# LTX-Rapidfire.net
KiCad netlist of a schematic drawn in EAGLE
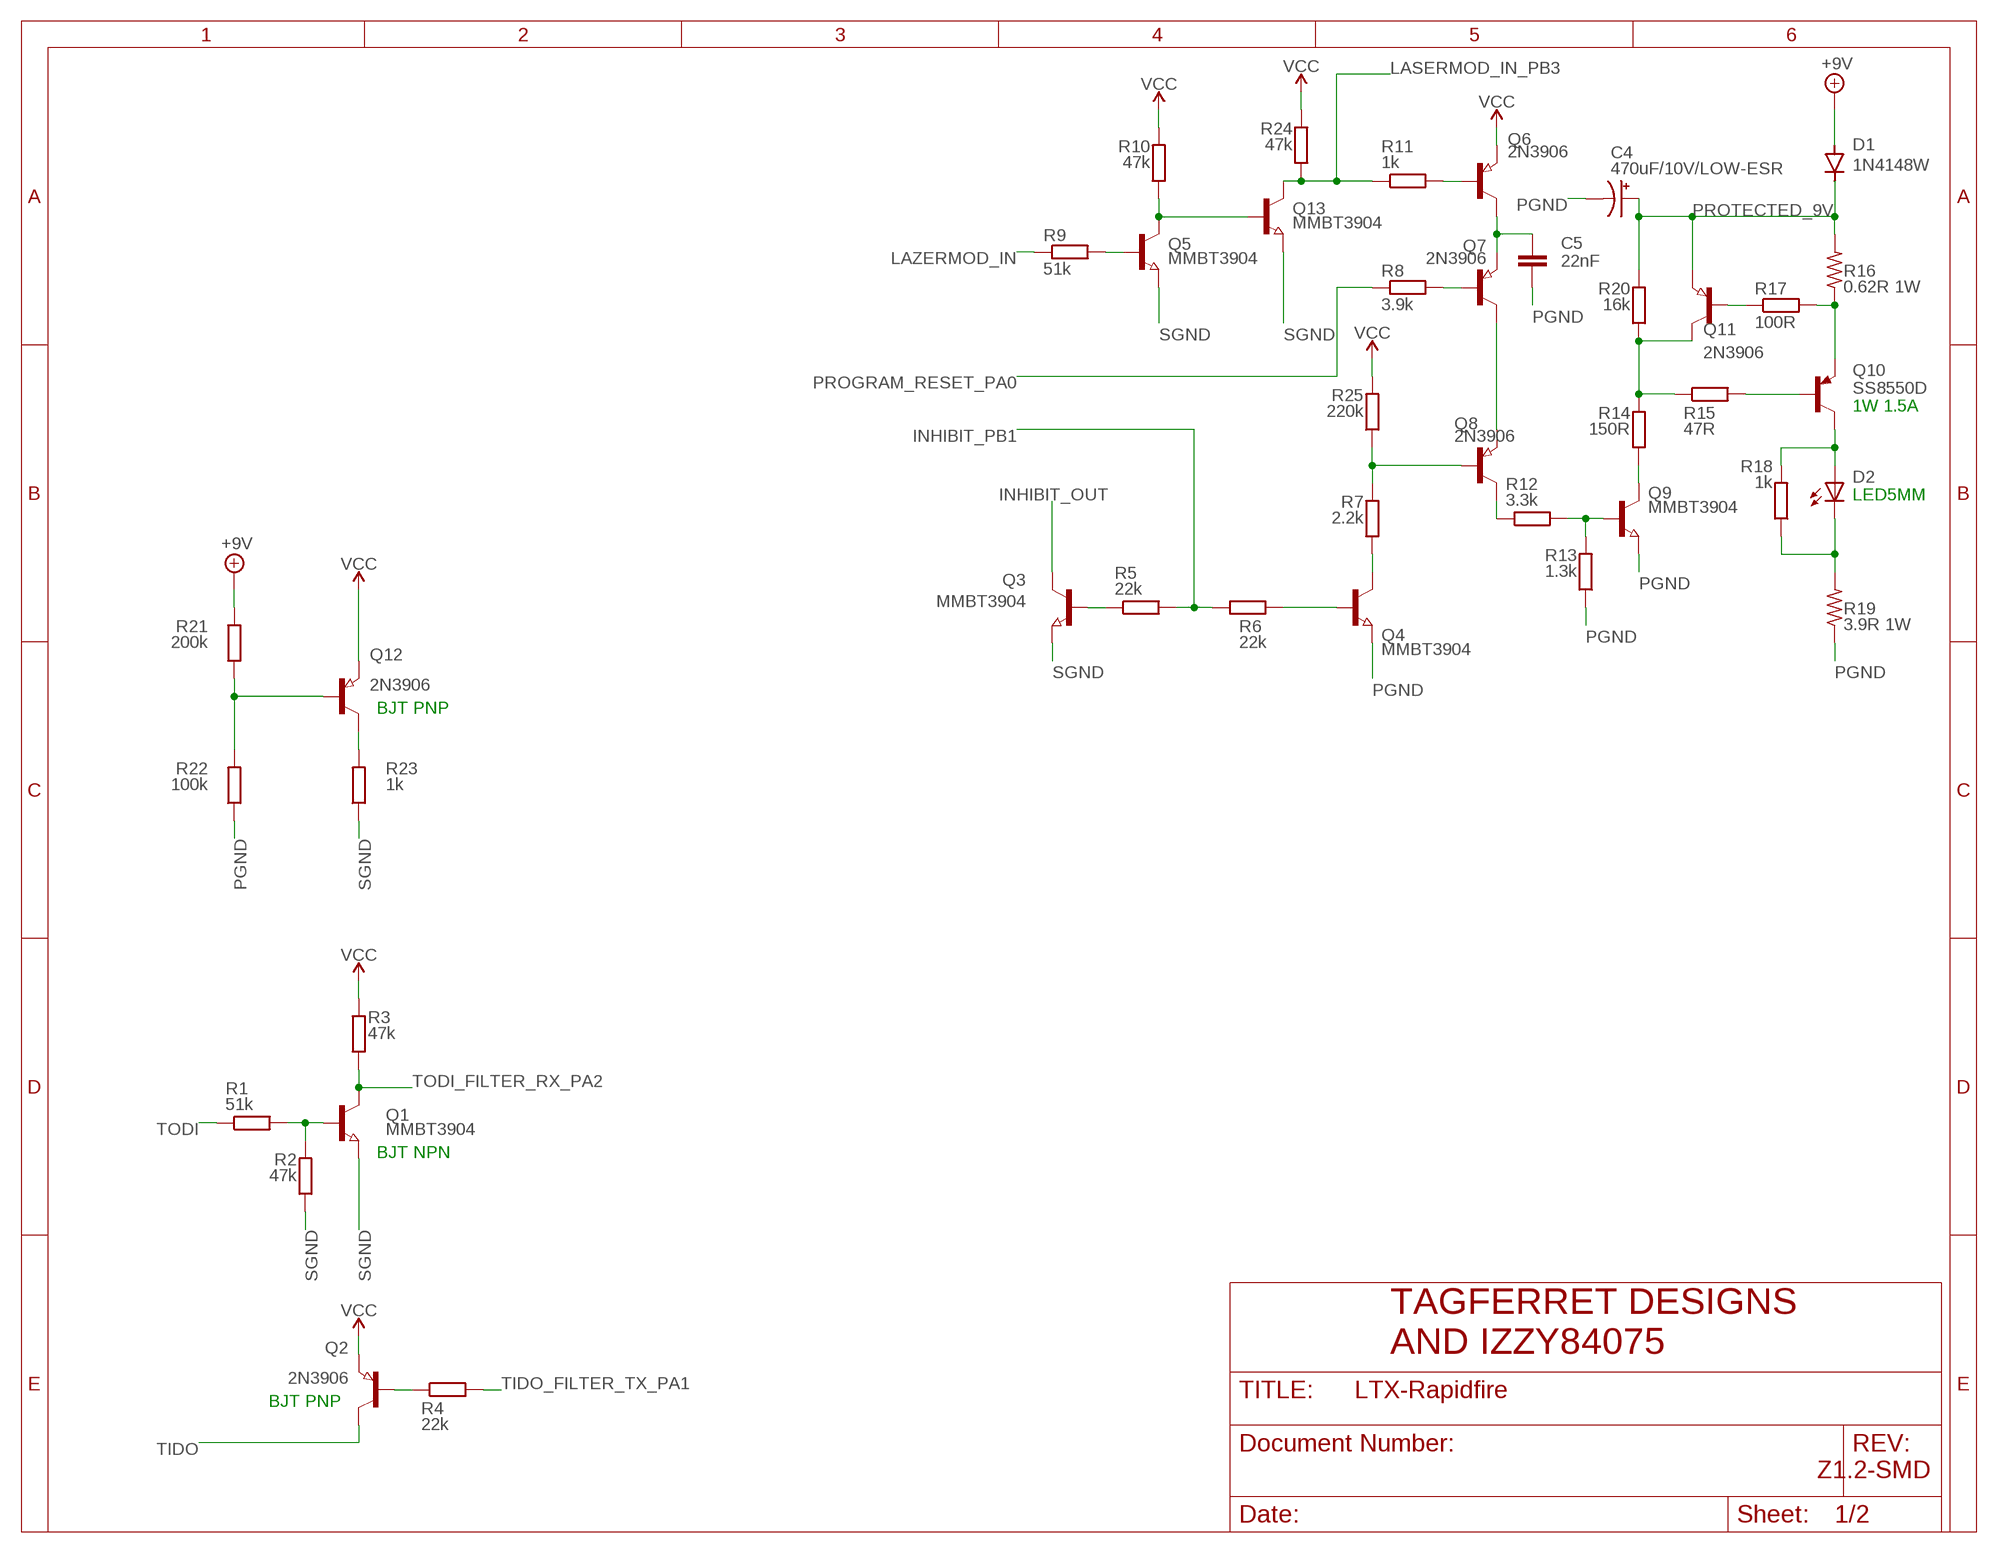
[diagram p0: schematic, sheet 1]
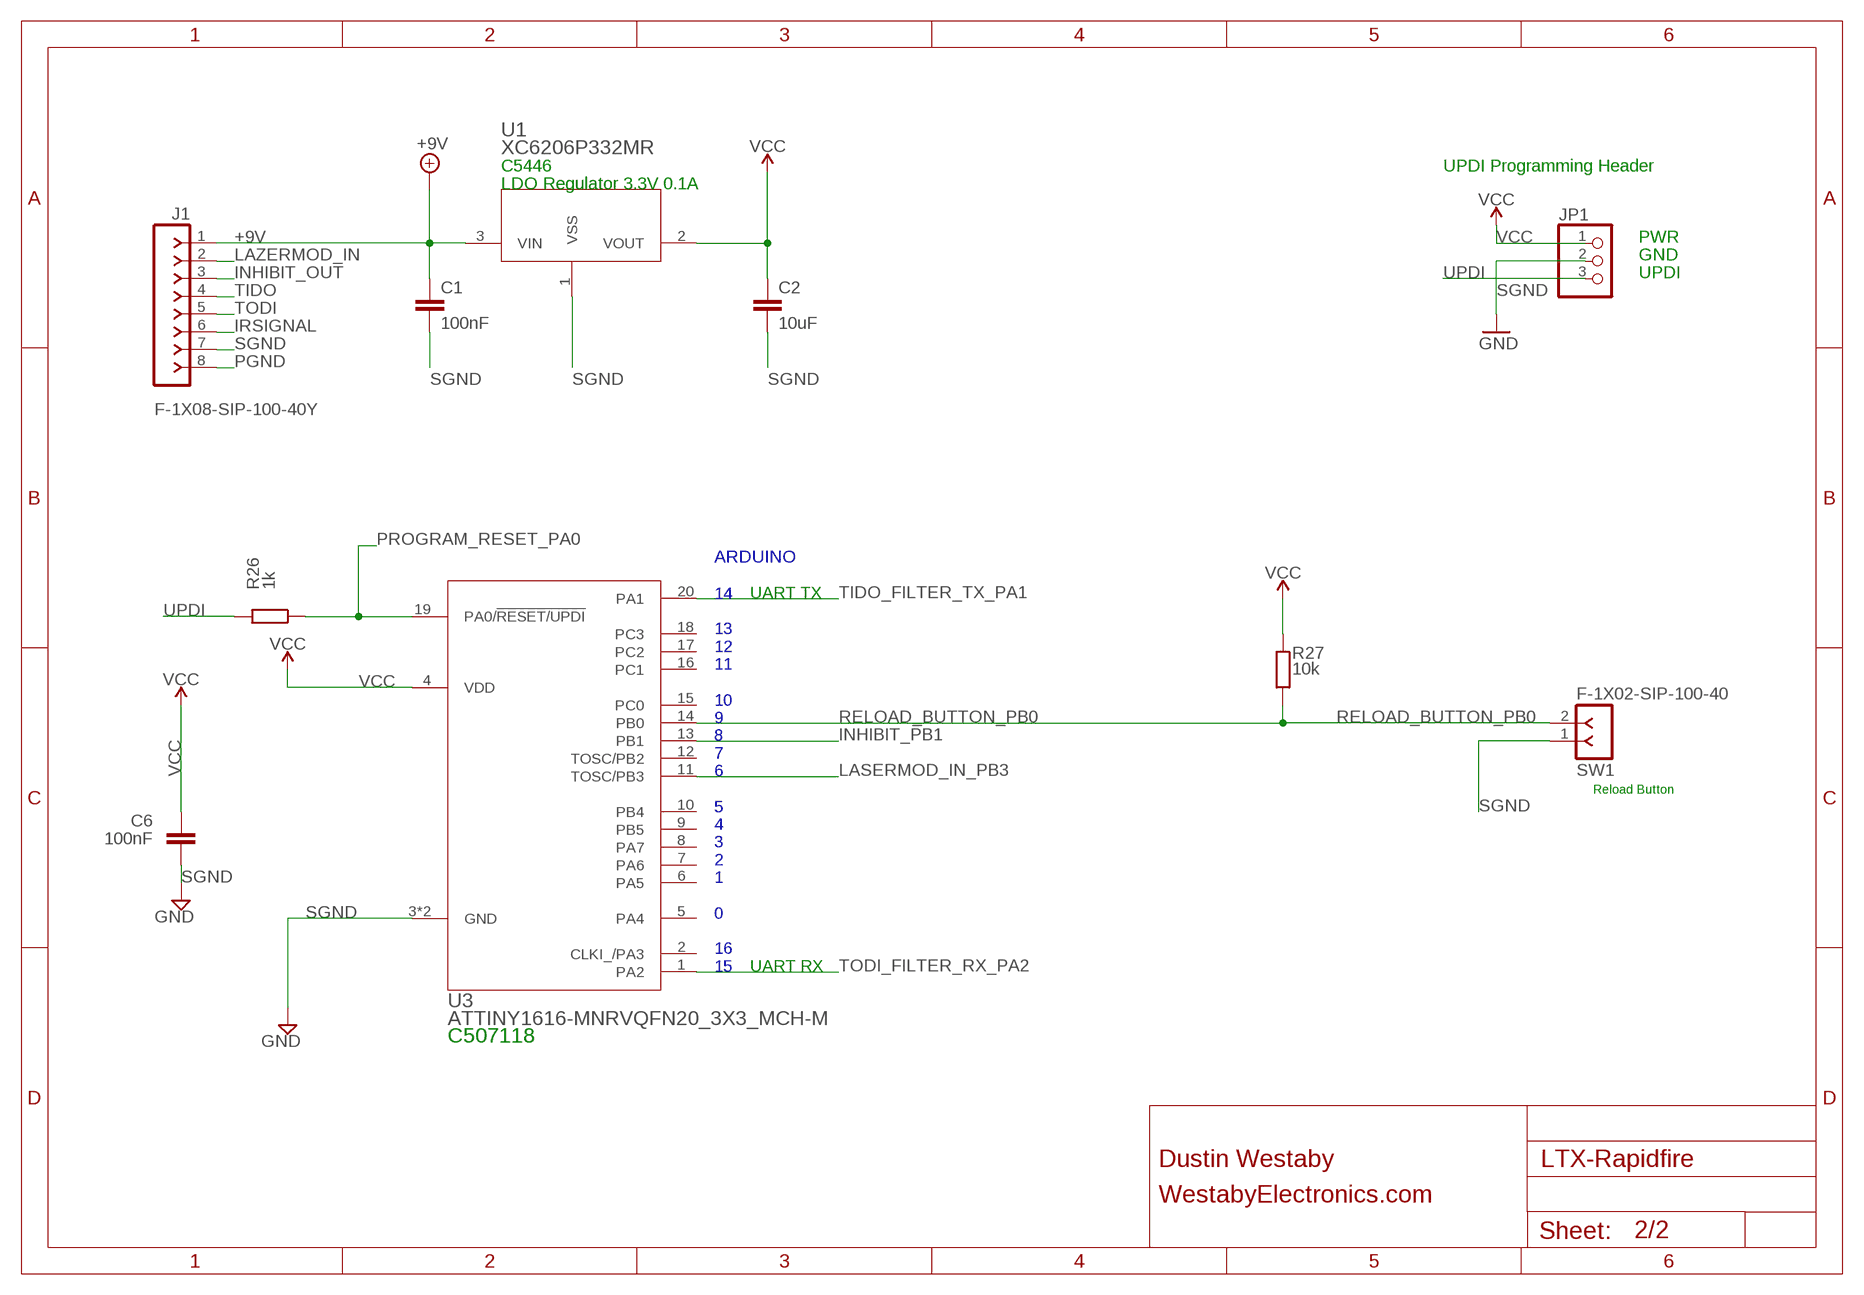
[diagram p1: schematic, sheet 2]

(export (version "E")
  (design (tool "Eeschema 10.0.6"))
  (components
    (comp (ref "C1")
      (value "100nF")
      (footprint "eagle-import:C0603")
      (fields (field (name "LCSC_PART") "C14663"))
      (libsource (lib "eagle-import") (part "C__0603100NF/50V"))
    )
    (comp (ref "C2")
      (value "10uF")
      (footprint "eagle-import:C0603")
      (fields (field (name "LCSC_PART") "C96446"))
      (libsource (lib "eagle-import") (part "C__060310UF/25V"))
    )
    (comp (ref "C6")
      (value "100nF")
      (footprint "eagle-import:C0603")
      (fields (field (name "LCSC_PART") "C14663"))
      (libsource (lib "eagle-import") (part "C__0603100NF/50V"))
    )
    (comp (ref "J1")
      (value "F-1X08-SIP-100-40Y")
      (footprint "eagle-import:SIP-100-08-40Y")
      (libsource (lib "eagle-import") (part "F-1X08-SIP-100-40Y"))
    )
    (comp (ref "JP1")
      (value "PINHD-1X3")
      (footprint "eagle-import:1X03")
      (libsource (lib "eagle-import") (part "PINHD-1X3"))
    )
    (comp (ref "R26")
      (value "1k")
      (footprint "eagle-import:R0603")
      (fields (field (name "LCSC_PART") "C21190"))
      (libsource (lib "eagle-import") (part "R__06031K"))
    )
    (comp (ref "R27")
      (value "10k")
      (footprint "eagle-import:R0603")
      (fields (field (name "LCSC_PART") "C25804"))
      (libsource (lib "eagle-import") (part "R__060310K"))
    )
    (comp (ref "SW1")
      (value "F-1X02-SIP-100-40")
      (footprint "eagle-import:SIP-100-02-40")
      (libsource (lib "eagle-import") (part "F-1X02-SIP-100-40"))
    )
    (comp (ref "U1")
      (value "XC6206P332MR")
      (footprint "eagle-import:SOT-23_TOR")
      (fields
        (field (name "LCSC_PART") "C5446")
        (field (name "COPYRIGHT") "Copyright (C) 2022 Ultra Librarian. All rights reserved.")
      )
      (libsource (lib "eagle-import") (part "XC6206P332MR"))
    )
    (comp (ref "U3")
      (value "ATTINY1616-MNRVQFN20_3X3_MCH-M")
      (footprint "eagle-import:VQFN20_3X3_MCH-M")
      (fields
        (field (name "MANUFACTURER_PART_NUMBER") "ATTINY1616-MNR")
        (field (name "COPYRIGHT") "Copyright (C) 2022 Ultra Librarian. All rights reserved.")
      )
      (libsource (lib "eagle-import") (part "ATTINY1616-MNRVQFN20_3X3_MCH-M"))
    )
    (comp (ref "C4")
      (value "470uF/10V/LOW-ESR")
      (footprint "eagle-import:E3,5-8")
      (fields (field (name "LCSC_PART") "C43332"))
      (libsource (lib "eagle-import") (part "CPOL-USE3.5-8"))
    )
    (comp (ref "C5")
      (value "22nF")
      (footprint "eagle-import:C0603")
      (fields (field (name "LCSC_PART") "C21122"))
      (libsource (lib "eagle-import") (part "C__060322NF/50V"))
    )
    (comp (ref "D1")
      (value "1N4148W")
      (footprint "eagle-import:SOD123")
      (fields (field (name "LCSC_PART") "C81598"))
      (libsource (lib "eagle-import") (part "D__SOD1231N4148W_ST"))
    )
    (comp (ref "D2")
      (value "LED5MM")
      (footprint "eagle-import:LED5MM")
      (libsource (lib "eagle-import") (part "LED5MM"))
    )
    (comp (ref "Q1")
      (value "MMBT3904")
      (footprint "eagle-import:SOT23")
      (fields (field (name "LCSC_PART") "C20526"))
      (libsource (lib "eagle-import") (part "T_NPN__SOT23-BECMMBT3904_CHANGJ"))
    )
    (comp (ref "Q2")
      (value "2N3906")
      (footprint "eagle-import:SOT23")
      (fields
        (field (name "LCSC_PART") "C8326")
        (field (name "LCSC_DATASHEET") "https://datasheet.lcsc.com/lcsc/1810111520_KEC-Semicon-2N3906S-RTK-P_C147294.pdf")
        (field (name "LCSC_PART_1") "C147294")
        (field (name "PROPERTIES") "40V 350mW 200mA 100@10mA,1V 250MHz 400mV@50mA,5mA PNP")
      )
      (libsource (lib "eagle-import") (part "T_PNP__SOT23-BECMMBT5401_CHANGJ"))
    )
    (comp (ref "Q3")
      (value "MMBT3904")
      (footprint "eagle-import:SOT23")
      (fields (field (name "LCSC_PART") "C20526"))
      (libsource (lib "eagle-import") (part "T_NPN__SOT23-BECMMBT3904_CHANGJ"))
    )
    (comp (ref "Q4")
      (value "MMBT3904")
      (footprint "eagle-import:SOT23")
      (fields (field (name "LCSC_PART") "C20526"))
      (libsource (lib "eagle-import") (part "T_NPN__SOT23-BECMMBT3904_CHANGJ"))
    )
    (comp (ref "Q5")
      (value "MMBT3904")
      (footprint "eagle-import:SOT23")
      (fields (field (name "LCSC_PART") "C20526"))
      (libsource (lib "eagle-import") (part "T_NPN__SOT23-BECMMBT3904_CHANGJ"))
    )
    (comp (ref "Q6")
      (value "2N3906")
      (footprint "eagle-import:SOT23")
      (fields
        (field (name "LCSC_PART") "C8326")
        (field (name "LCSC_DATASHEET") "https://datasheet.lcsc.com/lcsc/1810111520_KEC-Semicon-2N3906S-RTK-P_C147294.pdf")
        (field (name "LCSC_PART_1") "C147294")
        (field (name "PROPERTIES") "40V 350mW 200mA 100@10mA,1V 250MHz 400mV@50mA,5mA PNP")
      )
      (libsource (lib "eagle-import") (part "T_PNP__SOT23-BECMMBT5401_CHANGJ"))
    )
    (comp (ref "Q7")
      (value "2N3906")
      (footprint "eagle-import:SOT23")
      (fields
        (field (name "LCSC_PART") "C8326")
        (field (name "LCSC_DATASHEET") "https://datasheet.lcsc.com/lcsc/1810111520_KEC-Semicon-2N3906S-RTK-P_C147294.pdf")
        (field (name "LCSC_PART_1") "C147294")
        (field (name "PROPERTIES") "40V 350mW 200mA 100@10mA,1V 250MHz 400mV@50mA,5mA PNP")
      )
      (libsource (lib "eagle-import") (part "T_PNP__SOT23-BECMMBT5401_CHANGJ"))
    )
    (comp (ref "Q8")
      (value "2N3906")
      (footprint "eagle-import:SOT23")
      (fields
        (field (name "LCSC_PART") "C8326")
        (field (name "LCSC_DATASHEET") "https://datasheet.lcsc.com/lcsc/1810111520_KEC-Semicon-2N3906S-RTK-P_C147294.pdf")
        (field (name "LCSC_PART_1") "C147294")
        (field (name "PROPERTIES") "40V 350mW 200mA 100@10mA,1V 250MHz 400mV@50mA,5mA PNP")
      )
      (libsource (lib "eagle-import") (part "T_PNP__SOT23-BECMMBT5401_CHANGJ"))
    )
    (comp (ref "Q9")
      (value "MMBT3904")
      (footprint "eagle-import:SOT23")
      (fields (field (name "LCSC_PART") "C20526"))
      (libsource (lib "eagle-import") (part "T_NPN__SOT23-BECMMBT3904_CHANGJ"))
    )
    (comp (ref "Q10")
      (value "SS8550D")
      (footprint "eagle-import:TO92")
      (fields (field (name "LCSC_PART") "C118551"))
      (libsource (lib "eagle-import") (part "2N3906"))
    )
    (comp (ref "Q11")
      (value "2N3906")
      (footprint "eagle-import:SOT23")
      (fields
        (field (name "LCSC_PART") "C8326")
        (field (name "LCSC_DATASHEET") "https://datasheet.lcsc.com/lcsc/1810111520_KEC-Semicon-2N3906S-RTK-P_C147294.pdf")
        (field (name "LCSC_PART_1") "C147294")
        (field (name "PROPERTIES") "40V 350mW 200mA 100@10mA,1V 250MHz 400mV@50mA,5mA PNP")
      )
      (libsource (lib "eagle-import") (part "T_PNP__SOT23-BECMMBT5401_CHANGJ"))
    )
    (comp (ref "Q12")
      (value "2N3906")
      (footprint "eagle-import:SOT23")
      (fields
        (field (name "LCSC_PART") "C8326")
        (field (name "LCSC_DATASHEET") "https://datasheet.lcsc.com/lcsc/1810111520_KEC-Semicon-2N3906S-RTK-P_C147294.pdf")
        (field (name "LCSC_PART_1") "C147294")
        (field (name "PROPERTIES") "40V 350mW 200mA 100@10mA,1V 250MHz 400mV@50mA,5mA PNP")
      )
      (libsource (lib "eagle-import") (part "T_PNP__SOT23-BECMMBT5401_CHANGJ"))
    )
    (comp (ref "Q13")
      (value "MMBT3904")
      (footprint "eagle-import:SOT23")
      (fields (field (name "LCSC_PART") "C20526"))
      (libsource (lib "eagle-import") (part "T_NPN__SOT23-BECMMBT3904_CHANGJ"))
    )
    (comp (ref "R1")
      (value "51k")
      (footprint "eagle-import:R0603")
      (fields (field (name "LCSC_PART") "C23196"))
      (libsource (lib "eagle-import") (part "R__060351K"))
    )
    (comp (ref "R2")
      (value "47k")
      (footprint "eagle-import:R0603")
      (fields (field (name "LCSC_PART") "C25819"))
      (libsource (lib "eagle-import") (part "R__060347K"))
    )
    (comp (ref "R3")
      (value "47k")
      (footprint "eagle-import:R0603")
      (fields (field (name "LCSC_PART") "C25819"))
      (libsource (lib "eagle-import") (part "R__060347K"))
    )
    (comp (ref "R4")
      (value "22k")
      (footprint "eagle-import:R0603")
      (fields (field (name "LCSC_PART") "C31850"))
      (libsource (lib "eagle-import") (part "R__060322K"))
    )
    (comp (ref "R5")
      (value "22k")
      (footprint "eagle-import:R0603")
      (fields (field (name "LCSC_PART") "C31850"))
      (libsource (lib "eagle-import") (part "R__060322K"))
    )
    (comp (ref "R6")
      (value "22k")
      (footprint "eagle-import:R0603")
      (fields (field (name "LCSC_PART") "C31850"))
      (libsource (lib "eagle-import") (part "R__060322K"))
    )
    (comp (ref "R7")
      (value "2.2k")
      (footprint "eagle-import:R0603")
      (fields (field (name "LCSC_PART") "C4190"))
      (libsource (lib "eagle-import") (part "R__06032.2K"))
    )
    (comp (ref "R8")
      (value "3.9k")
      (footprint "eagle-import:R0603")
      (fields (field (name "LCSC_PART") "C23018"))
      (libsource (lib "eagle-import") (part "R__06033.9K"))
    )
    (comp (ref "R9")
      (value "51k")
      (footprint "eagle-import:R0603")
      (fields (field (name "LCSC_PART") "C23196"))
      (libsource (lib "eagle-import") (part "R__060351K"))
    )
    (comp (ref "R10")
      (value "47k")
      (footprint "eagle-import:R0603")
      (fields (field (name "LCSC_PART") "C25819"))
      (libsource (lib "eagle-import") (part "R__060347K"))
    )
    (comp (ref "R11")
      (value "1k")
      (footprint "eagle-import:R0603")
      (fields (field (name "LCSC_PART") "C21190"))
      (libsource (lib "eagle-import") (part "R__06031K"))
    )
    (comp (ref "R12")
      (value "3.3k")
      (footprint "eagle-import:R0603")
      (fields (field (name "LCSC_PART") "C22978"))
      (libsource (lib "eagle-import") (part "R__06033.3K"))
    )
    (comp (ref "R13")
      (value "1.3k")
      (footprint "eagle-import:R0603")
      (fields
        (field (name "LCSC_PART") "C4190")
        (field (name "LCSC_DATASHEET") "https://datasheet.lcsc.com/lcsc/2206010130_UNI-ROYAL-Uniroyal-Elec-0603WAF1301T5E_C22767.pdf")
        (field (name "LCSC_PART_1") "C22767")
        (field (name "PROPERTIES") "100mW Thick Film Resistors 75V ±100ppm/℃ ±1% -55℃~+155℃ 1.3kΩ")
      )
      (libsource (lib "eagle-import") (part "R__06032.2K"))
    )
    (comp (ref "R14")
      (value "150R")
      (footprint "eagle-import:R0603")
      (fields (field (name "LCSC_PART") "C22808"))
      (libsource (lib "eagle-import") (part "R__0603150R"))
    )
    (comp (ref "R15")
      (value "47R")
      (footprint "eagle-import:R0603")
      (fields (field (name "LCSC_PART") "C23182"))
      (libsource (lib "eagle-import") (part "R__060347R"))
    )
    (comp (ref "R16")
      (value "0.62R 1W")
      (footprint "eagle-import:R2512")
      (fields (field (name "LCSC_PART") "C705623"))
      (libsource (lib "eagle-import") (part "R-US_R2512"))
    )
    (comp (ref "R17")
      (value "100R")
      (footprint "eagle-import:R0603")
      (fields (field (name "LCSC_PART") "C22775"))
      (libsource (lib "eagle-import") (part "R__0603100R"))
    )
    (comp (ref "R18")
      (value "1k")
      (footprint "eagle-import:R0603")
      (fields (field (name "LCSC_PART") "C21190"))
      (libsource (lib "eagle-import") (part "R__06031K"))
    )
    (comp (ref "R19")
      (value "3.9R 1W")
      (footprint "eagle-import:R2512")
      (fields (field (name "LCSC_PART") "C66801"))
      (libsource (lib "eagle-import") (part "R-US_R2512"))
    )
    (comp (ref "R20")
      (value "16k")
      (footprint "eagle-import:R0805")
      (fields (field (name "LCSC_PART") "C17490"))
      (libsource (lib "eagle-import") (part "R__080516K"))
    )
    (comp (ref "R21")
      (value "200k")
      (footprint "eagle-import:R0603")
      (fields (field (name "LCSC_PART") "C25811"))
      (libsource (lib "eagle-import") (part "R__0603200K"))
    )
    (comp (ref "R22")
      (value "100k")
      (footprint "eagle-import:R0603")
      (fields (field (name "LCSC_PART") "C25803"))
      (libsource (lib "eagle-import") (part "R__0603100K"))
    )
    (comp (ref "R23")
      (value "1k")
      (footprint "eagle-import:R0603")
      (fields (field (name "LCSC_PART") "C21190"))
      (libsource (lib "eagle-import") (part "R__06031K"))
    )
    (comp (ref "R24")
      (value "47k")
      (footprint "eagle-import:R0603")
      (fields (field (name "LCSC_PART") "C25819"))
      (libsource (lib "eagle-import") (part "R__060347K"))
    )
    (comp (ref "R25")
      (value "220k")
      (footprint "eagle-import:R0603")
      (fields (field (name "LCSC_PART") "C22961"))
      (libsource (lib "eagle-import") (part "R__0603220K"))
    )
  )
  (nets
    (net (code "1") (name "+9V") (class "Default")
      (node (ref "C1") (pin "1") (pinfunction "1_1") (pintype "passive"))
      (node (ref "D1") (pin "A") (pinfunction "A_A") (pintype "passive"))
      (node (ref "J1") (pin "1") (pinfunction "1_1") (pintype "passive"))
      (node (ref "R21") (pin "2") (pinfunction "2_2") (pintype "passive"))
      (node (ref "U1") (pin "3") (pinfunction "VIN_3") (pintype "power_in"))
    )
    (net (code "2") (name "INHIBIT_OUT") (class "Default")
      (node (ref "J1") (pin "3") (pinfunction "3_3") (pintype "passive"))
      (node (ref "Q3") (pin "3") (pinfunction "C_3") (pintype "passive"))
    )
    (net (code "3") (name "INHIBIT_PB1") (class "Default")
      (node (ref "R5") (pin "2") (pinfunction "2_2") (pintype "passive"))
      (node (ref "R6") (pin "1") (pinfunction "1_1") (pintype "passive"))
      (node (ref "U3") (pin "13") (pinfunction "PB1_13") (pintype "bidirectional"))
    )
    (net (code "4") (name "IRSIGNAL") (class "Default")
      (node (ref "J1") (pin "6") (pinfunction "6_6") (pintype "passive"))
    )
    (net (code "5") (name "LASERMOD_IN_PB3") (class "Default")
      (node (ref "Q13") (pin "3") (pinfunction "C_3") (pintype "passive"))
      (node (ref "R11") (pin "1") (pinfunction "1_1") (pintype "passive"))
      (node (ref "R24") (pin "1") (pinfunction "1_1") (pintype "passive"))
      (node (ref "U3") (pin "11") (pinfunction "TOSC/PB3_11") (pintype "passive"))
    )
    (net (code "6") (name "LAZERMOD_IN") (class "Default")
      (node (ref "J1") (pin "2") (pinfunction "2_2") (pintype "passive"))
      (node (ref "R9") (pin "1") (pinfunction "1_1") (pintype "passive"))
    )
    (net (code "7") (name "Net-(D2-C)") (class "Default")
      (node (ref "D2") (pin "K") (pinfunction "C_K") (pintype "passive"))
      (node (ref "R18") (pin "1") (pinfunction "1_1") (pintype "passive"))
      (node (ref "R19") (pin "2") (pinfunction "2_2") (pintype "passive"))
    )
    (net (code "8") (name "Net-(Q1-B)") (class "Default")
      (node (ref "Q1") (pin "1") (pinfunction "B_1") (pintype "passive"))
      (node (ref "R1") (pin "2") (pinfunction "2_2") (pintype "passive"))
      (node (ref "R2") (pin "2") (pinfunction "2_2") (pintype "passive"))
    )
    (net (code "9") (name "Net-(Q2-B)") (class "Default")
      (node (ref "Q2") (pin "1") (pinfunction "B_1") (pintype "passive"))
      (node (ref "R4") (pin "1") (pinfunction "1_1") (pintype "passive"))
    )
    (net (code "10") (name "Net-(Q3-B)") (class "Default")
      (node (ref "Q3") (pin "1") (pinfunction "B_1") (pintype "passive"))
      (node (ref "R5") (pin "1") (pinfunction "1_1") (pintype "passive"))
    )
    (net (code "11") (name "Net-(Q4-B)") (class "Default")
      (node (ref "Q4") (pin "1") (pinfunction "B_1") (pintype "passive"))
      (node (ref "R6") (pin "2") (pinfunction "2_2") (pintype "passive"))
    )
    (net (code "12") (name "Net-(Q4-C)") (class "Default")
      (node (ref "Q4") (pin "3") (pinfunction "C_3") (pintype "passive"))
      (node (ref "R7") (pin "1") (pinfunction "1_1") (pintype "passive"))
    )
    (net (code "13") (name "Net-(Q5-B)") (class "Default")
      (node (ref "Q5") (pin "1") (pinfunction "B_1") (pintype "passive"))
      (node (ref "R9") (pin "2") (pinfunction "2_2") (pintype "passive"))
    )
    (net (code "14") (name "Net-(Q6-B)") (class "Default")
      (node (ref "Q6") (pin "1") (pinfunction "B_1") (pintype "passive"))
      (node (ref "R11") (pin "2") (pinfunction "2_2") (pintype "passive"))
    )
    (net (code "15") (name "Net-(Q6-C)") (class "Default")
      (node (ref "C5") (pin "1") (pinfunction "1_1") (pintype "passive"))
      (node (ref "Q6") (pin "3") (pinfunction "C_3") (pintype "passive"))
      (node (ref "Q7") (pin "2") (pinfunction "E_2") (pintype "passive"))
    )
    (net (code "16") (name "Net-(Q7-B)") (class "Default")
      (node (ref "Q7") (pin "1") (pinfunction "B_1") (pintype "passive"))
      (node (ref "R8") (pin "2") (pinfunction "2_2") (pintype "passive"))
    )
    (net (code "17") (name "Net-(Q7-C)") (class "Default")
      (node (ref "Q7") (pin "3") (pinfunction "C_3") (pintype "passive"))
      (node (ref "Q8") (pin "2") (pinfunction "E_2") (pintype "passive"))
    )
    (net (code "18") (name "Net-(Q8-B)") (class "Default")
      (node (ref "Q8") (pin "1") (pinfunction "B_1") (pintype "passive"))
      (node (ref "R25") (pin "1") (pinfunction "1_1") (pintype "passive"))
      (node (ref "R7") (pin "2") (pinfunction "2_2") (pintype "passive"))
    )
    (net (code "19") (name "Net-(Q8-C)") (class "Default")
      (node (ref "Q8") (pin "3") (pinfunction "C_3") (pintype "passive"))
      (node (ref "R12") (pin "1") (pinfunction "1_1") (pintype "passive"))
    )
    (net (code "20") (name "Net-(Q9-B)") (class "Default")
      (node (ref "Q9") (pin "1") (pinfunction "B_1") (pintype "passive"))
      (node (ref "R12") (pin "2") (pinfunction "2_2") (pintype "passive"))
      (node (ref "R13") (pin "2") (pinfunction "2_2") (pintype "passive"))
    )
    (net (code "21") (name "Net-(Q9-C)") (class "Default")
      (node (ref "Q9") (pin "3") (pinfunction "C_3") (pintype "passive"))
      (node (ref "R14") (pin "1") (pinfunction "1_1") (pintype "passive"))
    )
    (net (code "22") (name "Net-(Q10-B)") (class "Default")
      (node (ref "Q10") (pin "2") (pinfunction "B_2") (pintype "passive"))
      (node (ref "R15") (pin "2") (pinfunction "2_2") (pintype "passive"))
    )
    (net (code "23") (name "Net-(Q10-C)") (class "Default")
      (node (ref "D2") (pin "A") (pinfunction "A_A") (pintype "passive"))
      (node (ref "Q10") (pin "1") (pinfunction "C_1") (pintype "passive"))
      (node (ref "R18") (pin "2") (pinfunction "2_2") (pintype "passive"))
    )
    (net (code "24") (name "Net-(Q10-E)") (class "Default")
      (node (ref "Q10") (pin "3") (pinfunction "E_3") (pintype "passive"))
      (node (ref "R16") (pin "1") (pinfunction "1_1") (pintype "passive"))
      (node (ref "R17") (pin "2") (pinfunction "2_2") (pintype "passive"))
    )
    (net (code "25") (name "Net-(Q11-B)") (class "Default")
      (node (ref "Q11") (pin "1") (pinfunction "B_1") (pintype "passive"))
      (node (ref "R17") (pin "1") (pinfunction "1_1") (pintype "passive"))
    )
    (net (code "26") (name "Net-(Q11-C)") (class "Default")
      (node (ref "Q11") (pin "3") (pinfunction "C_3") (pintype "passive"))
      (node (ref "R14") (pin "2") (pinfunction "2_2") (pintype "passive"))
      (node (ref "R15") (pin "1") (pinfunction "1_1") (pintype "passive"))
      (node (ref "R20") (pin "1") (pinfunction "1_1") (pintype "passive"))
    )
    (net (code "27") (name "Net-(Q12-B)") (class "Default")
      (node (ref "Q12") (pin "1") (pinfunction "B_1") (pintype "passive"))
      (node (ref "R21") (pin "1") (pinfunction "1_1") (pintype "passive"))
      (node (ref "R22") (pin "2") (pinfunction "2_2") (pintype "passive"))
    )
    (net (code "28") (name "Net-(Q12-C)") (class "Default")
      (node (ref "Q12") (pin "3") (pinfunction "C_3") (pintype "passive"))
      (node (ref "R23") (pin "2") (pinfunction "2_2") (pintype "passive"))
    )
    (net (code "29") (name "Net-(Q13-B)") (class "Default")
      (node (ref "Q13") (pin "1") (pinfunction "B_1") (pintype "passive"))
      (node (ref "Q5") (pin "3") (pinfunction "C_3") (pintype "passive"))
      (node (ref "R10") (pin "1") (pinfunction "1_1") (pintype "passive"))
    )
    (net (code "30") (name "PGND") (class "Default")
      (node (ref "C4") (pin "-") (pinfunction "-_-") (pintype "passive"))
      (node (ref "C5") (pin "2") (pinfunction "2_2") (pintype "passive"))
      (node (ref "J1") (pin "8") (pinfunction "8_8") (pintype "passive"))
      (node (ref "Q4") (pin "2") (pinfunction "E_2") (pintype "passive"))
      (node (ref "Q9") (pin "2") (pinfunction "E_2") (pintype "passive"))
      (node (ref "R13") (pin "1") (pinfunction "1_1") (pintype "passive"))
      (node (ref "R19") (pin "1") (pinfunction "1_1") (pintype "passive"))
      (node (ref "R22") (pin "1") (pinfunction "1_1") (pintype "passive"))
    )
    (net (code "31") (name "PROGRAM_RESET_PA0") (class "Default")
      (node (ref "R26") (pin "1") (pinfunction "1_1") (pintype "passive"))
      (node (ref "R8") (pin "1") (pinfunction "1_1") (pintype "passive"))
      (node (ref "U3") (pin "19") (pinfunction "PA0/~{RESET/UPDI}_19") (pintype "bidirectional"))
    )
    (net (code "32") (name "PROTECTED_9V") (class "Default")
      (node (ref "C4") (pin "+") (pinfunction "+_+") (pintype "passive"))
      (node (ref "D1") (pin "C") (pinfunction "C_C") (pintype "passive"))
      (node (ref "Q11") (pin "2") (pinfunction "E_2") (pintype "passive"))
      (node (ref "R16") (pin "2") (pinfunction "2_2") (pintype "passive"))
      (node (ref "R20") (pin "2") (pinfunction "2_2") (pintype "passive"))
    )
    (net (code "33") (name "RELOAD_BUTTON_PB0") (class "Default")
      (node (ref "R27") (pin "2") (pinfunction "2_2") (pintype "passive"))
      (node (ref "SW1") (pin "2") (pinfunction "2_2") (pintype "passive"))
      (node (ref "U3") (pin "14") (pinfunction "PB0_14") (pintype "bidirectional"))
    )
    (net (code "34") (name "SGND") (class "Default")
      (node (ref "C1") (pin "2") (pinfunction "2_2") (pintype "passive"))
      (node (ref "C2") (pin "2") (pinfunction "2_2") (pintype "passive"))
      (node (ref "C6") (pin "2") (pinfunction "2_2") (pintype "passive"))
      (node (ref "J1") (pin "7") (pinfunction "7_7") (pintype "passive"))
      (node (ref "JP1") (pin "2") (pinfunction "2_2") (pintype "passive"))
      (node (ref "Q1") (pin "2") (pinfunction "E_2") (pintype "passive"))
      (node (ref "Q13") (pin "2") (pinfunction "E_2") (pintype "passive"))
      (node (ref "Q3") (pin "2") (pinfunction "E_2") (pintype "passive"))
      (node (ref "Q5") (pin "2") (pinfunction "E_2") (pintype "passive"))
      (node (ref "R2") (pin "1") (pinfunction "1_1") (pintype "passive"))
      (node (ref "R23") (pin "1") (pinfunction "1_1") (pintype "passive"))
      (node (ref "SW1") (pin "1") (pinfunction "1_1") (pintype "passive"))
      (node (ref "U1") (pin "1") (pinfunction "VSS_1") (pintype "passive"))
      (node (ref "U3") (pin "21") (pinfunction "GND_21") (pintype "passive"))
      (node (ref "U3") (pin "3") (pinfunction "GND_3") (pintype "passive"))
    )
    (net (code "35") (name "TIDO") (class "Default")
      (node (ref "J1") (pin "4") (pinfunction "4_4") (pintype "passive"))
      (node (ref "Q2") (pin "3") (pinfunction "C_3") (pintype "passive"))
    )
    (net (code "36") (name "TIDO_FILTER_TX_PA1") (class "Default")
      (node (ref "R4") (pin "2") (pinfunction "2_2") (pintype "passive"))
      (node (ref "U3") (pin "20") (pinfunction "PA1_20") (pintype "bidirectional"))
    )
    (net (code "37") (name "TODI") (class "Default")
      (node (ref "J1") (pin "5") (pinfunction "5_5") (pintype "passive"))
      (node (ref "R1") (pin "1") (pinfunction "1_1") (pintype "passive"))
    )
    (net (code "38") (name "TODI_FILTER_RX_PA2") (class "Default")
      (node (ref "Q1") (pin "3") (pinfunction "C_3") (pintype "passive"))
      (node (ref "R3") (pin "1") (pinfunction "1_1") (pintype "passive"))
      (node (ref "U3") (pin "1") (pinfunction "PA2_1") (pintype "bidirectional"))
    )
    (net (code "39") (name "UPDI") (class "Default")
      (node (ref "JP1") (pin "3") (pinfunction "3_3") (pintype "passive"))
      (node (ref "R26") (pin "2") (pinfunction "2_2") (pintype "passive"))
    )
    (net (code "40") (name "VCC") (class "Default")
      (node (ref "C2") (pin "1") (pinfunction "1_1") (pintype "passive"))
      (node (ref "C6") (pin "1") (pinfunction "1_1") (pintype "passive"))
      (node (ref "JP1") (pin "1") (pinfunction "1_1") (pintype "passive"))
      (node (ref "Q12") (pin "2") (pinfunction "E_2") (pintype "passive"))
      (node (ref "Q2") (pin "2") (pinfunction "E_2") (pintype "passive"))
      (node (ref "Q6") (pin "2") (pinfunction "E_2") (pintype "passive"))
      (node (ref "R10") (pin "2") (pinfunction "2_2") (pintype "passive"))
      (node (ref "R24") (pin "2") (pinfunction "2_2") (pintype "passive"))
      (node (ref "R25") (pin "2") (pinfunction "2_2") (pintype "passive"))
      (node (ref "R27") (pin "1") (pinfunction "1_1") (pintype "passive"))
      (node (ref "R3") (pin "2") (pinfunction "2_2") (pintype "passive"))
      (node (ref "U1") (pin "2") (pinfunction "VOUT_2") (pintype "output"))
      (node (ref "U3") (pin "4") (pinfunction "VDD_4") (pintype "power_in"))
    )
    (net (code "41") (name "unconnected-(U3-CLKI_{slash}PA3-Pad2)") (class "Default")
      (node (ref "U3") (pin "2") (pinfunction "CLKI_/PA3_2") (pintype "passive"))
    )
    (net (code "42") (name "unconnected-(U3-PA4-Pad5)") (class "Default")
      (node (ref "U3") (pin "5") (pinfunction "PA4_5") (pintype "bidirectional"))
    )
    (net (code "43") (name "unconnected-(U3-PA5-Pad6)") (class "Default")
      (node (ref "U3") (pin "6") (pinfunction "PA5_6") (pintype "bidirectional"))
    )
    (net (code "44") (name "unconnected-(U3-PA6-Pad7)") (class "Default")
      (node (ref "U3") (pin "7") (pinfunction "PA6_7") (pintype "bidirectional"))
    )
    (net (code "45") (name "unconnected-(U3-PA7-Pad8)") (class "Default")
      (node (ref "U3") (pin "8") (pinfunction "PA7_8") (pintype "bidirectional"))
    )
    (net (code "46") (name "unconnected-(U3-PB4-Pad10)") (class "Default")
      (node (ref "U3") (pin "10") (pinfunction "PB4_10") (pintype "bidirectional"))
    )
    (net (code "47") (name "unconnected-(U3-PB5-Pad9)") (class "Default")
      (node (ref "U3") (pin "9") (pinfunction "PB5_9") (pintype "bidirectional"))
    )
    (net (code "48") (name "unconnected-(U3-PC0-Pad15)") (class "Default")
      (node (ref "U3") (pin "15") (pinfunction "PC0_15") (pintype "bidirectional"))
    )
    (net (code "49") (name "unconnected-(U3-PC1-Pad16)") (class "Default")
      (node (ref "U3") (pin "16") (pinfunction "PC1_16") (pintype "bidirectional"))
    )
    (net (code "50") (name "unconnected-(U3-PC2-Pad17)") (class "Default")
      (node (ref "U3") (pin "17") (pinfunction "PC2_17") (pintype "bidirectional"))
    )
    (net (code "51") (name "unconnected-(U3-PC3-Pad18)") (class "Default")
      (node (ref "U3") (pin "18") (pinfunction "PC3_18") (pintype "bidirectional"))
    )
    (net (code "52") (name "unconnected-(U3-TOSC{slash}PB2-Pad12)") (class "Default")
      (node (ref "U3") (pin "12") (pinfunction "TOSC/PB2_12") (pintype "bidirectional"))
    )
  )
)
